# DAC.net
KiCad netlist of a schematic drawn in Altium Designer
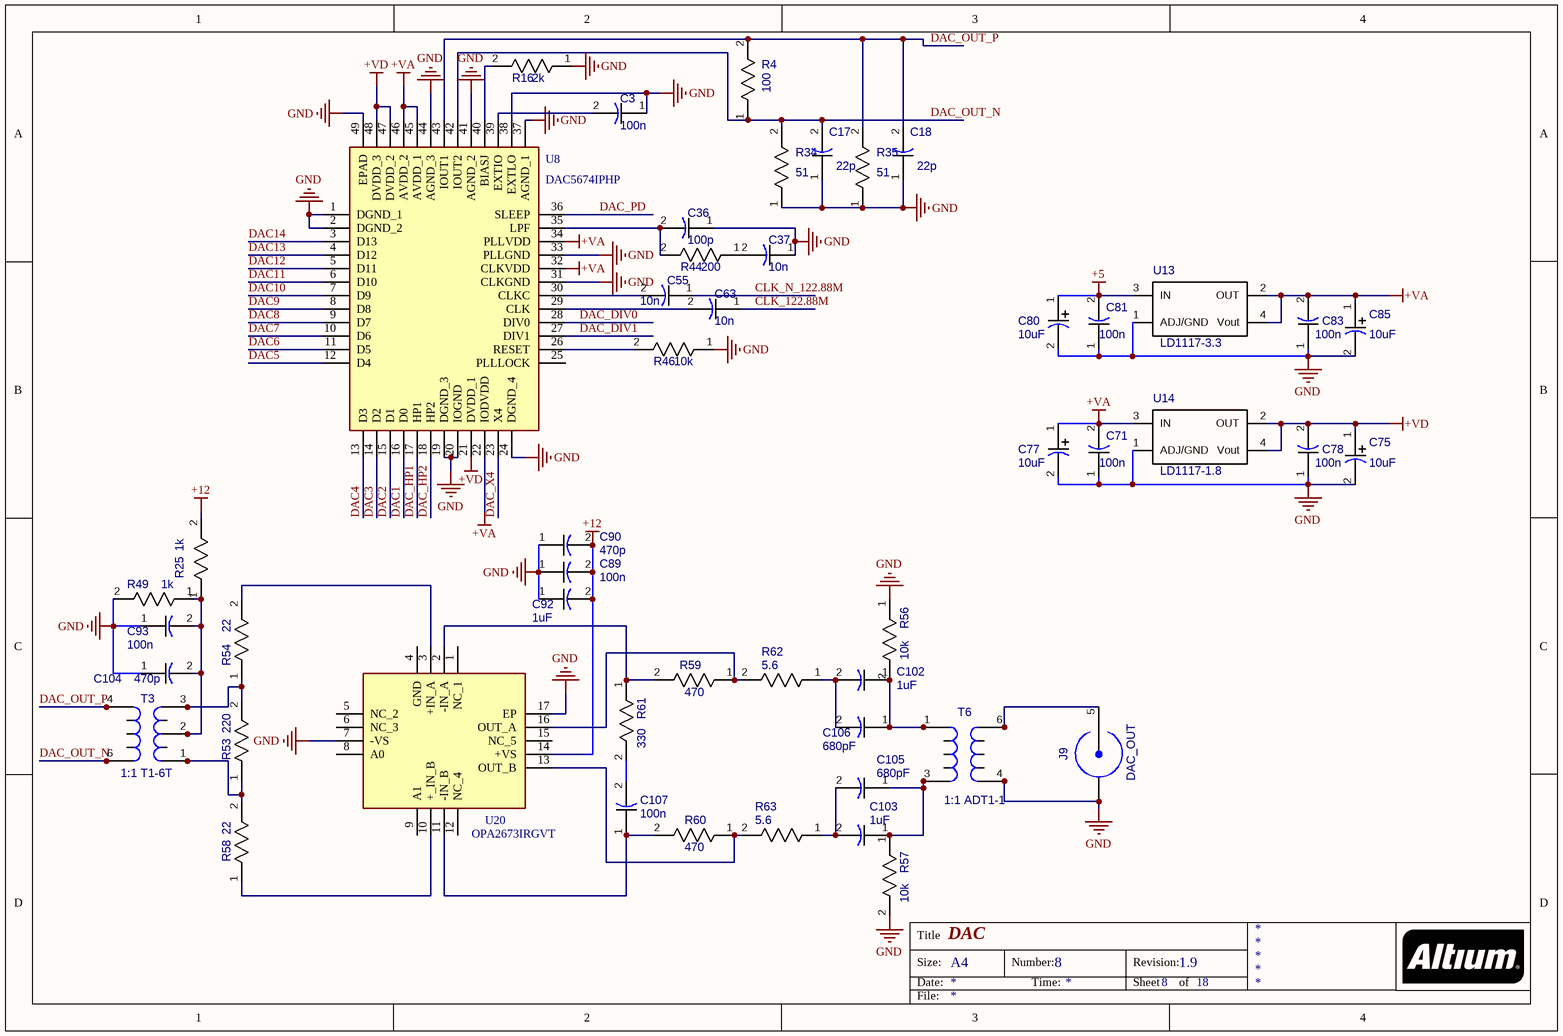
[diagram p0: DAC.SchDoc]

(export (version "E")
  (design (tool "Eeschema 10.0.6"))
  (components
    (comp (ref "C3")
      (value "100n")
      (footprint "CAP_0805")
      (description "CAP_0805")
      (libsource (lib "*") (part "CAP_0805"))
    )
    (comp (ref "C17")
      (value "22p")
      (footprint "CAP_0805")
      (description "CAP_0805")
      (libsource (lib "*") (part "CAP_0805"))
    )
    (comp (ref "C18")
      (value "22p")
      (footprint "CAP_0805")
      (description "CAP_0805")
      (libsource (lib "*") (part "CAP_0805"))
    )
    (comp (ref "C36")
      (value "100p")
      (footprint "CAP_0805")
      (description "CAP_0805")
      (libsource (lib "*") (part "CAP_0805"))
    )
    (comp (ref "C37")
      (value "10n")
      (footprint "CAP_0805")
      (description "CAP_0805")
      (libsource (lib "*") (part "CAP_0805"))
    )
    (comp (ref "C55")
      (value "10n")
      (footprint "CAP_0805")
      (description "CAP_0805")
      (libsource (lib "*") (part "CAP_0805"))
    )
    (comp (ref "C63")
      (value "10n")
      (footprint "CAP_0805")
      (description "CAP_0805")
      (libsource (lib "*") (part "CAP_0805"))
    )
    (comp (ref "C71")
      (value "100n")
      (footprint "CAP_0805")
      (description "CAP_0805")
      (libsource (lib "*") (part "CAP_0805"))
    )
    (comp (ref "C75")
      (value "10uF")
      (footprint "EEEFC_sizeB")
      (description "EEEFC_sizeB")
      (libsource (lib "*") (part "EEEFC_sizeB"))
    )
    (comp (ref "C77")
      (value "10uF")
      (footprint "EEEFC_sizeB")
      (description "EEEFC_sizeB")
      (libsource (lib "*") (part "EEEFC_sizeB"))
    )
    (comp (ref "C78")
      (value "100n")
      (footprint "CAP_0805")
      (description "CAP_0805")
      (libsource (lib "*") (part "CAP_0805"))
    )
    (comp (ref "C80")
      (value "10uF")
      (footprint "EEEFC_sizeB")
      (description "EEEFC_sizeB")
      (libsource (lib "*") (part "EEEFC_sizeB"))
    )
    (comp (ref "C81")
      (value "100n")
      (footprint "CAP_0805")
      (description "CAP_0805")
      (libsource (lib "*") (part "CAP_0805"))
    )
    (comp (ref "C83")
      (value "100n")
      (footprint "CAP_0805")
      (description "CAP_0805")
      (libsource (lib "*") (part "CAP_0805"))
    )
    (comp (ref "C85")
      (value "10uF")
      (footprint "EEEFC_sizeB")
      (description "EEEFC_sizeB")
      (libsource (lib "*") (part "EEEFC_sizeB"))
    )
    (comp (ref "C89")
      (value "100n")
      (footprint "CAP_0805")
      (description "CAP_0805")
      (libsource (lib "*") (part "CAP_0805"))
    )
    (comp (ref "C90")
      (value "470p")
      (footprint "CAP_0805")
      (description "CAP_0805")
      (libsource (lib "*") (part "CAP_0805"))
    )
    (comp (ref "C92")
      (value "1uF")
      (footprint "CAP_0805")
      (description "CAP_0805")
      (libsource (lib "*") (part "CAP_0805"))
    )
    (comp (ref "C93")
      (value "100n")
      (footprint "CAP_0805")
      (description "CAP_0805")
      (libsource (lib "*") (part "CAP_0805"))
    )
    (comp (ref "C102")
      (value "1uF")
      (footprint "CAP_1206")
      (description "CAP_1206")
      (libsource (lib "*") (part "CAP_1206"))
    )
    (comp (ref "C103")
      (value "1uF")
      (footprint "CAP_1206")
      (description "CAP_1206")
      (libsource (lib "*") (part "CAP_1206"))
    )
    (comp (ref "C104")
      (value "470p")
      (footprint "CAP_0805")
      (description "CAP_0805")
      (libsource (lib "*") (part "CAP_0805"))
    )
    (comp (ref "C105")
      (value "680pF")
      (footprint "CAP_1206")
      (description "CAP_1206")
      (libsource (lib "*") (part "CAP_1206"))
    )
    (comp (ref "C106")
      (value "680pF")
      (footprint "CAP_1206")
      (description "CAP_1206")
      (libsource (lib "*") (part "CAP_1206"))
    )
    (comp (ref "C107")
      (value "100n")
      (footprint "CAP_0805")
      (description "CAP_0805")
      (libsource (lib "*") (part "CAP_0805"))
    )
    (comp (ref "J9")
      (value "DAC_OUT")
      (footprint "31-5431")
      (description "31-5431")
      (libsource (lib "RF-UNIT_1") (part "31-5431"))
    )
    (comp (ref "R4")
      (value "100")
      (footprint "RES_0805")
      (description "RES_0805")
      (libsource (lib "*") (part "RES_0805"))
    )
    (comp (ref "R16")
      (value "2k")
      (footprint "RES_0805")
      (description "RES_0805")
      (libsource (lib "*") (part "RES_0805"))
    )
    (comp (ref "R25")
      (value "1k")
      (footprint "RES_0805")
      (description "RES_0805")
      (libsource (lib "*") (part "RES_0805"))
    )
    (comp (ref "R34")
      (value "51")
      (footprint "RES_0805")
      (description "RES_0805")
      (libsource (lib "*") (part "RES_0805"))
    )
    (comp (ref "R35")
      (value "51")
      (footprint "RES_0805")
      (description "RES_0805")
      (libsource (lib "*") (part "RES_0805"))
    )
    (comp (ref "R44")
      (value "200")
      (footprint "RES_0805")
      (description "RES_0805")
      (libsource (lib "*") (part "RES_0805"))
    )
    (comp (ref "R46")
      (value "10k")
      (footprint "RES_0805")
      (description "RES_0805")
      (libsource (lib "*") (part "RES_0805"))
    )
    (comp (ref "R49")
      (value "1k")
      (footprint "RES_0805")
      (description "RES_0805")
      (libsource (lib "*") (part "RES_0805"))
    )
    (comp (ref "R53")
      (value "220")
      (footprint "RES_0805")
      (description "RES_0805")
      (libsource (lib "*") (part "RES_0805"))
    )
    (comp (ref "R54")
      (value "22")
      (footprint "RES_0805")
      (description "RES_0805")
      (libsource (lib "*") (part "RES_0805"))
    )
    (comp (ref "R56")
      (value "10k")
      (footprint "RES_0805")
      (description "RES_0805")
      (libsource (lib "*") (part "RES_0805"))
    )
    (comp (ref "R57")
      (value "10k")
      (footprint "RES_0805")
      (description "RES_0805")
      (libsource (lib "*") (part "RES_0805"))
    )
    (comp (ref "R58")
      (value "22")
      (footprint "RES_0805")
      (description "RES_0805")
      (libsource (lib "*") (part "RES_0805"))
    )
    (comp (ref "R59")
      (value "470")
      (footprint "RES_0805")
      (description "RES_0805")
      (libsource (lib "*") (part "RES_0805"))
    )
    (comp (ref "R60")
      (value "470")
      (footprint "RES_0805")
      (description "RES_0805")
      (libsource (lib "*") (part "RES_0805"))
    )
    (comp (ref "R61")
      (value "330")
      (footprint "RES_0805")
      (description "RES_0805")
      (libsource (lib "*") (part "RES_0805"))
    )
    (comp (ref "R62")
      (value "5.6")
      (footprint "RES_1206")
      (description "RES_1206")
      (libsource (lib "*") (part "RES_1206"))
    )
    (comp (ref "R63")
      (value "5.6")
      (footprint "RES_1206")
      (description "RES_1206")
      (libsource (lib "*") (part "RES_1206"))
    )
    (comp (ref "T3")
      (value "1:1 T1-6T")
      (footprint "TRANSF_ACORE2")
      (description "Transformer")
      (libsource (lib "MOTHERBOARD_1") (part "TRANSF_ACORE2"))
    )
    (comp (ref "T6")
      (value "1:1 ADT1-1")
      (footprint "TRANSF_ACORE")
      (description "Transformer")
      (libsource (lib "MOTHERBOARD_1") (part "TRANSF_ACORE"))
    )
    (comp (ref "U8")
      (value "DAC5674IPHP")
      (footprint "SamacSys:QFP50P900X900X100-49N")
      (description "Integrated Circuit")
      (libsource (lib "*") (part "DAC5674IPHP"))
    )
    (comp (ref "U13")
      (value "LD1117-3.3")
      (footprint "LT1117CST-3.3")
      (description "LT1117CST-3.3")
      (libsource (lib "*") (part "LT1117CST-3.3"))
    )
    (comp (ref "U14")
      (value "LD1117-1.8")
      (footprint "LT1117CST-3.3")
      (description "LT1117CST-1.8")
      (libsource (lib "*") (part "LT1117CST-3.3"))
    )
    (comp (ref "U20")
      (value "OPA2673IRGVT")
      (footprint "SamacSys:QFN65P400X400X100-17N-D")
      (description "Integrated Circuit")
      (fields
        (field (name "MOUSER PART NUMBER") "595-OPA2673IRGVT")
        (field (name "RS PART NUMBER") "8122587P")
      )
      (libsource (lib "*") (part "OPA2673IRGVT"))
    )
  )
  (nets
    (net (code "1") (name "+5") (class "Default")
      (node (ref "C80") (pin "1") (pinfunction "PLUS_1") (pintype "passive"))
      (node (ref "C81") (pin "2") (pinfunction "2_2") (pintype "passive"))
      (node (ref "U13") (pin "3") (pinfunction "IN_3") (pintype "passive"))
    )
    (net (code "2") (name "+12") (class "Default")
      (node (ref "C89") (pin "2") (pinfunction "2_2") (pintype "passive"))
      (node (ref "C90") (pin "2") (pinfunction "2_2") (pintype "passive"))
      (node (ref "C92") (pin "2") (pinfunction "2_2") (pintype "passive"))
      (node (ref "R25") (pin "2") (pinfunction "2_2") (pintype "passive"))
      (node (ref "U20") (pin "14") (pinfunction "+VS_14") (pintype "passive"))
    )
    (net (code "3") (name "+VA") (class "Default")
      (node (ref "C71") (pin "2") (pinfunction "2_2") (pintype "passive"))
      (node (ref "C77") (pin "1") (pinfunction "PLUS_1") (pintype "passive"))
      (node (ref "C83") (pin "2") (pinfunction "2_2") (pintype "passive"))
      (node (ref "C85") (pin "1") (pinfunction "PLUS_1") (pintype "passive"))
      (node (ref "U13") (pin "2") (pinfunction "OUT_2") (pintype "passive"))
      (node (ref "U13") (pin "4") (pinfunction "Vout_4") (pintype "passive"))
      (node (ref "U14") (pin "3") (pinfunction "IN_3") (pintype "passive"))
      (node (ref "U8") (pin "22") (pinfunction "IODVDD_22") (pintype "passive"))
      (node (ref "U8") (pin "32") (pinfunction "CLKVDD_32") (pintype "passive"))
      (node (ref "U8") (pin "34") (pinfunction "PLLVDD_34") (pintype "passive"))
      (node (ref "U8") (pin "45") (pinfunction "AVDD_1_45") (pintype "passive"))
      (node (ref "U8") (pin "46") (pinfunction "AVDD_2_46") (pintype "passive"))
    )
    (net (code "4") (name "+VD") (class "Default")
      (node (ref "C75") (pin "1") (pinfunction "PLUS_1") (pintype "passive"))
      (node (ref "C78") (pin "2") (pinfunction "2_2") (pintype "passive"))
      (node (ref "U14") (pin "2") (pinfunction "OUT_2") (pintype "passive"))
      (node (ref "U14") (pin "4") (pinfunction "Vout_4") (pintype "passive"))
      (node (ref "U8") (pin "21") (pinfunction "DVDD_1_21") (pintype "passive"))
      (node (ref "U8") (pin "47") (pinfunction "DVDD_2_47") (pintype "passive"))
      (node (ref "U8") (pin "48") (pinfunction "DVDD_3_48") (pintype "passive"))
    )
    (net (code "5") (name "/CLK_122.88M") (class "Default")
      (node (ref "C63") (pin "1") (pinfunction "1_1") (pintype "passive"))
    )
    (net (code "6") (name "/CLK_N_122.88M") (class "Default")
      (node (ref "C55") (pin "1") (pinfunction "1_1") (pintype "passive"))
    )
    (net (code "7") (name "/DAC1") (class "Default")
      (node (ref "U8") (pin "16") (pinfunction "D0_16") (pintype "passive"))
    )
    (net (code "8") (name "/DAC2") (class "Default")
      (node (ref "U8") (pin "15") (pinfunction "D1_15") (pintype "passive"))
    )
    (net (code "9") (name "/DAC3") (class "Default")
      (node (ref "U8") (pin "14") (pinfunction "D2_14") (pintype "passive"))
    )
    (net (code "10") (name "/DAC4") (class "Default")
      (node (ref "U8") (pin "13") (pinfunction "D3_13") (pintype "passive"))
    )
    (net (code "11") (name "/DAC5") (class "Default")
      (node (ref "U8") (pin "12") (pinfunction "D4_12") (pintype "passive"))
    )
    (net (code "12") (name "/DAC6") (class "Default")
      (node (ref "U8") (pin "11") (pinfunction "D5_11") (pintype "passive"))
    )
    (net (code "13") (name "/DAC7") (class "Default")
      (node (ref "U8") (pin "10") (pinfunction "D6_10") (pintype "passive"))
    )
    (net (code "14") (name "/DAC8") (class "Default")
      (node (ref "U8") (pin "9") (pinfunction "D7_9") (pintype "passive"))
    )
    (net (code "15") (name "/DAC9") (class "Default")
      (node (ref "U8") (pin "8") (pinfunction "D8_8") (pintype "passive"))
    )
    (net (code "16") (name "/DAC10") (class "Default")
      (node (ref "U8") (pin "7") (pinfunction "D9_7") (pintype "passive"))
    )
    (net (code "17") (name "/DAC11") (class "Default")
      (node (ref "U8") (pin "6") (pinfunction "D10_6") (pintype "passive"))
    )
    (net (code "18") (name "/DAC12") (class "Default")
      (node (ref "U8") (pin "5") (pinfunction "D11_5") (pintype "passive"))
    )
    (net (code "19") (name "/DAC13") (class "Default")
      (node (ref "U8") (pin "4") (pinfunction "D12_4") (pintype "passive"))
    )
    (net (code "20") (name "/DAC14") (class "Default")
      (node (ref "U8") (pin "3") (pinfunction "D13_3") (pintype "passive"))
    )
    (net (code "21") (name "/DAC_DIV0") (class "Default")
      (node (ref "U8") (pin "28") (pinfunction "DIV0_28") (pintype "passive"))
    )
    (net (code "22") (name "/DAC_DIV1") (class "Default")
      (node (ref "U8") (pin "27") (pinfunction "DIV1_27") (pintype "passive"))
    )
    (net (code "23") (name "/DAC_HP1") (class "Default")
      (node (ref "U8") (pin "17") (pinfunction "HP1_17") (pintype "passive"))
    )
    (net (code "24") (name "/DAC_HP2") (class "Default")
      (node (ref "U8") (pin "18") (pinfunction "HP2_18") (pintype "passive"))
    )
    (net (code "25") (name "/DAC_OUT_N") (class "Default")
      (node (ref "C17") (pin "2") (pinfunction "2_2") (pintype "passive"))
      (node (ref "R34") (pin "2") (pinfunction "2_2") (pintype "passive"))
      (node (ref "R4") (pin "1") (pinfunction "1_1") (pintype "passive"))
      (node (ref "T3") (pin "10") (pinfunction "0_10") (pintype "passive"))
      (node (ref "T3") (pin "6") (pinfunction "P2_6") (pintype "passive"))
      (node (ref "U8") (pin "42") (pinfunction "IOUT2_42") (pintype "passive"))
    )
    (net (code "26") (name "/DAC_OUT_P") (class "Default")
      (node (ref "C18") (pin "2") (pinfunction "2_2") (pintype "passive"))
      (node (ref "R35") (pin "2") (pinfunction "2_2") (pintype "passive"))
      (node (ref "R4") (pin "2") (pinfunction "2_2") (pintype "passive"))
      (node (ref "T3") (pin "11") (pinfunction "0_11") (pintype "passive"))
      (node (ref "T3") (pin "4") (pinfunction "P1_4") (pintype "passive"))
      (node (ref "U8") (pin "43") (pinfunction "IOUT1_43") (pintype "passive"))
    )
    (net (code "27") (name "/DAC_PD") (class "Default")
      (node (ref "U8") (pin "36") (pinfunction "SLEEP_36") (pintype "passive"))
    )
    (net (code "28") (name "/DAC_X4") (class "Default")
      (node (ref "U8") (pin "23") (pinfunction "X4_23") (pintype "passive"))
    )
    (net (code "29") (name "GND") (class "Default")
      (node (ref "C104") (pin "1") (pinfunction "1_1") (pintype "passive"))
      (node (ref "C17") (pin "1") (pinfunction "1_1") (pintype "passive"))
      (node (ref "C18") (pin "1") (pinfunction "1_1") (pintype "passive"))
      (node (ref "C3") (pin "1") (pinfunction "1_1") (pintype "passive"))
      (node (ref "C36") (pin "1") (pinfunction "1_1") (pintype "passive"))
      (node (ref "C37") (pin "1") (pinfunction "1_1") (pintype "passive"))
      (node (ref "C71") (pin "1") (pinfunction "1_1") (pintype "passive"))
      (node (ref "C75") (pin "2") (pinfunction "MINUS_2") (pintype "passive"))
      (node (ref "C77") (pin "2") (pinfunction "MINUS_2") (pintype "passive"))
      (node (ref "C78") (pin "1") (pinfunction "1_1") (pintype "passive"))
      (node (ref "C80") (pin "2") (pinfunction "MINUS_2") (pintype "passive"))
      (node (ref "C81") (pin "1") (pinfunction "1_1") (pintype "passive"))
      (node (ref "C83") (pin "1") (pinfunction "1_1") (pintype "passive"))
      (node (ref "C85") (pin "2") (pinfunction "MINUS_2") (pintype "passive"))
      (node (ref "C89") (pin "1") (pinfunction "1_1") (pintype "passive"))
      (node (ref "C90") (pin "1") (pinfunction "1_1") (pintype "passive"))
      (node (ref "C92") (pin "1") (pinfunction "1_1") (pintype "passive"))
      (node (ref "C93") (pin "1") (pinfunction "1_1") (pintype "passive"))
      (node (ref "J9") (pin "1") (pinfunction "GND_1") (pintype "passive"))
      (node (ref "J9") (pin "2") (pinfunction "GND_2") (pintype "passive"))
      (node (ref "J9") (pin "3") (pinfunction "GND_3") (pintype "passive"))
      (node (ref "J9") (pin "4") (pinfunction "GND_4") (pintype "passive"))
      (node (ref "R16") (pin "1") (pinfunction "1_1") (pintype "passive"))
      (node (ref "R34") (pin "1") (pinfunction "1_1") (pintype "passive"))
      (node (ref "R35") (pin "1") (pinfunction "1_1") (pintype "passive"))
      (node (ref "R46") (pin "1") (pinfunction "1_1") (pintype "passive"))
      (node (ref "R49") (pin "2") (pinfunction "2_2") (pintype "passive"))
      (node (ref "R56") (pin "1") (pinfunction "1_1") (pintype "passive"))
      (node (ref "R57") (pin "2") (pinfunction "2_2") (pintype "passive"))
      (node (ref "T6") (pin "11") (pinfunction "0_11") (pintype "passive"))
      (node (ref "T6") (pin "4") (pinfunction "S2_4") (pintype "passive"))
      (node (ref "U13") (pin "1") (pinfunction "ADJ/GND_1") (pintype "passive"))
      (node (ref "U14") (pin "1") (pinfunction "ADJ/GND_1") (pintype "passive"))
      (node (ref "U20") (pin "17") (pinfunction "EP_17") (pintype "passive"))
      (node (ref "U20") (pin "7") (pinfunction "-VS_7") (pintype "passive"))
      (node (ref "U8") (pin "1") (pinfunction "DGND_1_1") (pintype "passive"))
      (node (ref "U8") (pin "19") (pinfunction "DGND_3_19") (pintype "passive"))
      (node (ref "U8") (pin "2") (pinfunction "DGND_2_2") (pintype "passive"))
      (node (ref "U8") (pin "20") (pinfunction "IOGND_20") (pintype "passive"))
      (node (ref "U8") (pin "24") (pinfunction "DGND_4_24") (pintype "passive"))
      (node (ref "U8") (pin "31") (pinfunction "CLKGND_31") (pintype "passive"))
      (node (ref "U8") (pin "33") (pinfunction "PLLGND_33") (pintype "passive"))
      (node (ref "U8") (pin "37") (pinfunction "AGND_1_37") (pintype "passive"))
      (node (ref "U8") (pin "38") (pinfunction "EXTLO_38") (pintype "passive"))
      (node (ref "U8") (pin "41") (pinfunction "AGND_2_41") (pintype "passive"))
      (node (ref "U8") (pin "44") (pinfunction "AGND_3_44") (pintype "passive"))
      (node (ref "U8") (pin "49") (pinfunction "EPAD_49") (pintype "passive"))
    )
    (net (code "30") (name "Net-(C37-Pad2)") (class "Default")
      (node (ref "C37") (pin "2") (pinfunction "2_2") (pintype "passive"))
      (node (ref "R44") (pin "1") (pinfunction "1_1") (pintype "passive"))
    )
    (net (code "31") (name "Net-(C102-Pad2)") (class "Default")
      (node (ref "C102") (pin "2") (pinfunction "2_2") (pintype "passive"))
      (node (ref "C106") (pin "2") (pinfunction "2_2") (pintype "passive"))
      (node (ref "R62") (pin "1") (pinfunction "1_1") (pintype "passive"))
    )
    (net (code "32") (name "Net-(C103-Pad2)") (class "Default")
      (node (ref "C103") (pin "2") (pinfunction "2_2") (pintype "passive"))
      (node (ref "C105") (pin "2") (pinfunction "2_2") (pintype "passive"))
      (node (ref "R63") (pin "1") (pinfunction "1_1") (pintype "passive"))
    )
    (net (code "33") (name "Net-(C107-Pad2)") (class "Default")
      (node (ref "C107") (pin "2") (pinfunction "2_2") (pintype "passive"))
      (node (ref "R61") (pin "2") (pinfunction "2_2") (pintype "passive"))
    )
    (net (code "34") (name "Net-(J9-CON)") (class "Default")
      (node (ref "J9") (pin "5") (pinfunction "CON_5") (pintype "passive"))
      (node (ref "T6") (pin "10") (pinfunction "0_10") (pintype "passive"))
      (node (ref "T6") (pin "6") (pinfunction "S1_6") (pintype "passive"))
    )
    (net (code "35") (name "Net-(T3-S1)") (class "Default")
      (node (ref "R53") (pin "2") (pinfunction "2_2") (pintype "passive"))
      (node (ref "R54") (pin "1") (pinfunction "1_1") (pintype "passive"))
      (node (ref "T3") (pin "3") (pinfunction "S1_3") (pintype "passive"))
      (node (ref "T3") (pin "9") (pinfunction "0_9") (pintype "passive"))
    )
    (net (code "36") (name "Net-(T3-S2)") (class "Default")
      (node (ref "C104") (pin "2") (pinfunction "2_2") (pintype "passive"))
      (node (ref "C93") (pin "2") (pinfunction "2_2") (pintype "passive"))
      (node (ref "R25") (pin "1") (pinfunction "1_1") (pintype "passive"))
      (node (ref "R49") (pin "1") (pinfunction "1_1") (pintype "passive"))
      (node (ref "T3") (pin "2") (pinfunction "S2_2") (pintype "passive"))
      (node (ref "T3") (pin "8") (pinfunction "0_8") (pintype "passive"))
    )
    (net (code "37") (name "Net-(T3-S3)") (class "Default")
      (node (ref "R53") (pin "1") (pinfunction "1_1") (pintype "passive"))
      (node (ref "R58") (pin "2") (pinfunction "2_2") (pintype "passive"))
      (node (ref "T3") (pin "1") (pinfunction "S3_1") (pintype "passive"))
      (node (ref "T3") (pin "7") (pinfunction "0_7") (pintype "passive"))
    )
    (net (code "38") (name "Net-(T6-P1)") (class "Default")
      (node (ref "C102") (pin "1") (pinfunction "1_1") (pintype "passive"))
      (node (ref "C106") (pin "1") (pinfunction "1_1") (pintype "passive"))
      (node (ref "R56") (pin "2") (pinfunction "2_2") (pintype "passive"))
      (node (ref "T6") (pin "1") (pinfunction "P1_1") (pintype "passive"))
      (node (ref "T6") (pin "7") (pinfunction "0_7") (pintype "passive"))
    )
    (net (code "39") (name "Net-(T6-P2)") (class "Default")
      (node (ref "C103") (pin "1") (pinfunction "1_1") (pintype "passive"))
      (node (ref "C105") (pin "1") (pinfunction "1_1") (pintype "passive"))
      (node (ref "R57") (pin "1") (pinfunction "1_1") (pintype "passive"))
      (node (ref "T6") (pin "3") (pinfunction "P2_3") (pintype "passive"))
      (node (ref "T6") (pin "9") (pinfunction "0_9") (pintype "passive"))
    )
    (net (code "40") (name "Net-(U8-BIASJ)") (class "Default")
      (node (ref "R16") (pin "2") (pinfunction "2_2") (pintype "passive"))
      (node (ref "U8") (pin "40") (pinfunction "BIASJ_40") (pintype "passive"))
    )
    (net (code "41") (name "Net-(U8-CLK)") (class "Default")
      (node (ref "C63") (pin "2") (pinfunction "2_2") (pintype "passive"))
      (node (ref "U8") (pin "29") (pinfunction "CLK_29") (pintype "passive"))
    )
    (net (code "42") (name "Net-(U8-CLKC)") (class "Default")
      (node (ref "C55") (pin "2") (pinfunction "2_2") (pintype "passive"))
      (node (ref "U8") (pin "30") (pinfunction "CLKC_30") (pintype "passive"))
    )
    (net (code "43") (name "Net-(U8-EXTIO)") (class "Default")
      (node (ref "C3") (pin "2") (pinfunction "2_2") (pintype "passive"))
      (node (ref "U8") (pin "39") (pinfunction "EXTIO_39") (pintype "passive"))
    )
    (net (code "44") (name "Net-(U8-LPF)") (class "Default")
      (node (ref "C36") (pin "2") (pinfunction "2_2") (pintype "passive"))
      (node (ref "R44") (pin "2") (pinfunction "2_2") (pintype "passive"))
      (node (ref "U8") (pin "35") (pinfunction "LPF_35") (pintype "passive"))
    )
    (net (code "45") (name "Net-(U8-RESET)") (class "Default")
      (node (ref "R46") (pin "2") (pinfunction "2_2") (pintype "passive"))
      (node (ref "U8") (pin "26") (pinfunction "RESET_26") (pintype "passive"))
    )
    (net (code "46") (name "Net-(U20-+IN_A)") (class "Default")
      (node (ref "R54") (pin "2") (pinfunction "2_2") (pintype "passive"))
      (node (ref "U20") (pin "3") (pinfunction "+IN_A_3") (pintype "passive"))
    )
    (net (code "47") (name "Net-(U20-+_IN_B)") (class "Default")
      (node (ref "R58") (pin "1") (pinfunction "1_1") (pintype "passive"))
      (node (ref "U20") (pin "10") (pinfunction "+_IN_B_10") (pintype "passive"))
    )
    (net (code "48") (name "Net-(U20--IN_A)") (class "Default")
      (node (ref "R59") (pin "2") (pinfunction "2_2") (pintype "passive"))
      (node (ref "R61") (pin "1") (pinfunction "1_1") (pintype "passive"))
      (node (ref "U20") (pin "2") (pinfunction "-IN_A_2") (pintype "passive"))
    )
    (net (code "49") (name "Net-(U20--IN_B)") (class "Default")
      (node (ref "C107") (pin "1") (pinfunction "1_1") (pintype "passive"))
      (node (ref "R60") (pin "2") (pinfunction "2_2") (pintype "passive"))
      (node (ref "U20") (pin "11") (pinfunction "-IN_B_11") (pintype "passive"))
    )
    (net (code "50") (name "Net-(U20-OUT_A)") (class "Default")
      (node (ref "R59") (pin "1") (pinfunction "1_1") (pintype "passive"))
      (node (ref "R62") (pin "2") (pinfunction "2_2") (pintype "passive"))
      (node (ref "U20") (pin "16") (pinfunction "OUT_A_16") (pintype "passive"))
    )
    (net (code "51") (name "Net-(U20-OUT_B)") (class "Default")
      (node (ref "R60") (pin "1") (pinfunction "1_1") (pintype "passive"))
      (node (ref "R63") (pin "2") (pinfunction "2_2") (pintype "passive"))
      (node (ref "U20") (pin "13") (pinfunction "OUT_B_13") (pintype "passive"))
    )
    (net (code "52") (name "unconnected-(T6-0-Pad8)") (class "Default")
      (node (ref "T6") (pin "8") (pinfunction "0_8") (pintype "passive"))
    )
    (net (code "53") (name "unconnected-(U8-PLLLOCK-Pad25)") (class "Default")
      (node (ref "U8") (pin "25") (pinfunction "PLLLOCK_25") (pintype "passive"))
    )
    (net (code "54") (name "unconnected-(U20-A0-Pad8)") (class "Default")
      (node (ref "U20") (pin "8") (pinfunction "A0_8") (pintype "passive"))
    )
    (net (code "55") (name "unconnected-(U20-A1-Pad9)") (class "Default")
      (node (ref "U20") (pin "9") (pinfunction "A1_9") (pintype "passive"))
    )
    (net (code "56") (name "unconnected-(U20-GND-Pad4)") (class "Default")
      (node (ref "U20") (pin "4") (pinfunction "GND_4") (pintype "passive"))
    )
    (net (code "57") (name "unconnected-(U20-NC_1-Pad1)") (class "Default")
      (node (ref "U20") (pin "1") (pinfunction "NC_1_1") (pintype "passive"))
    )
    (net (code "58") (name "unconnected-(U20-NC_2-Pad5)") (class "Default")
      (node (ref "U20") (pin "5") (pinfunction "NC_2_5") (pintype "passive"))
    )
    (net (code "59") (name "unconnected-(U20-NC_3-Pad6)") (class "Default")
      (node (ref "U20") (pin "6") (pinfunction "NC_3_6") (pintype "passive"))
    )
    (net (code "60") (name "unconnected-(U20-NC_4-Pad12)") (class "Default")
      (node (ref "U20") (pin "12") (pinfunction "NC_4_12") (pintype "passive"))
    )
    (net (code "61") (name "unconnected-(U20-NC_5-Pad15)") (class "Default")
      (node (ref "U20") (pin "15") (pinfunction "NC_5_15") (pintype "passive"))
    )
  )
)
